# BQH_DATN_PI4.net
KiCad netlist of a schematic drawn in Altium Designer
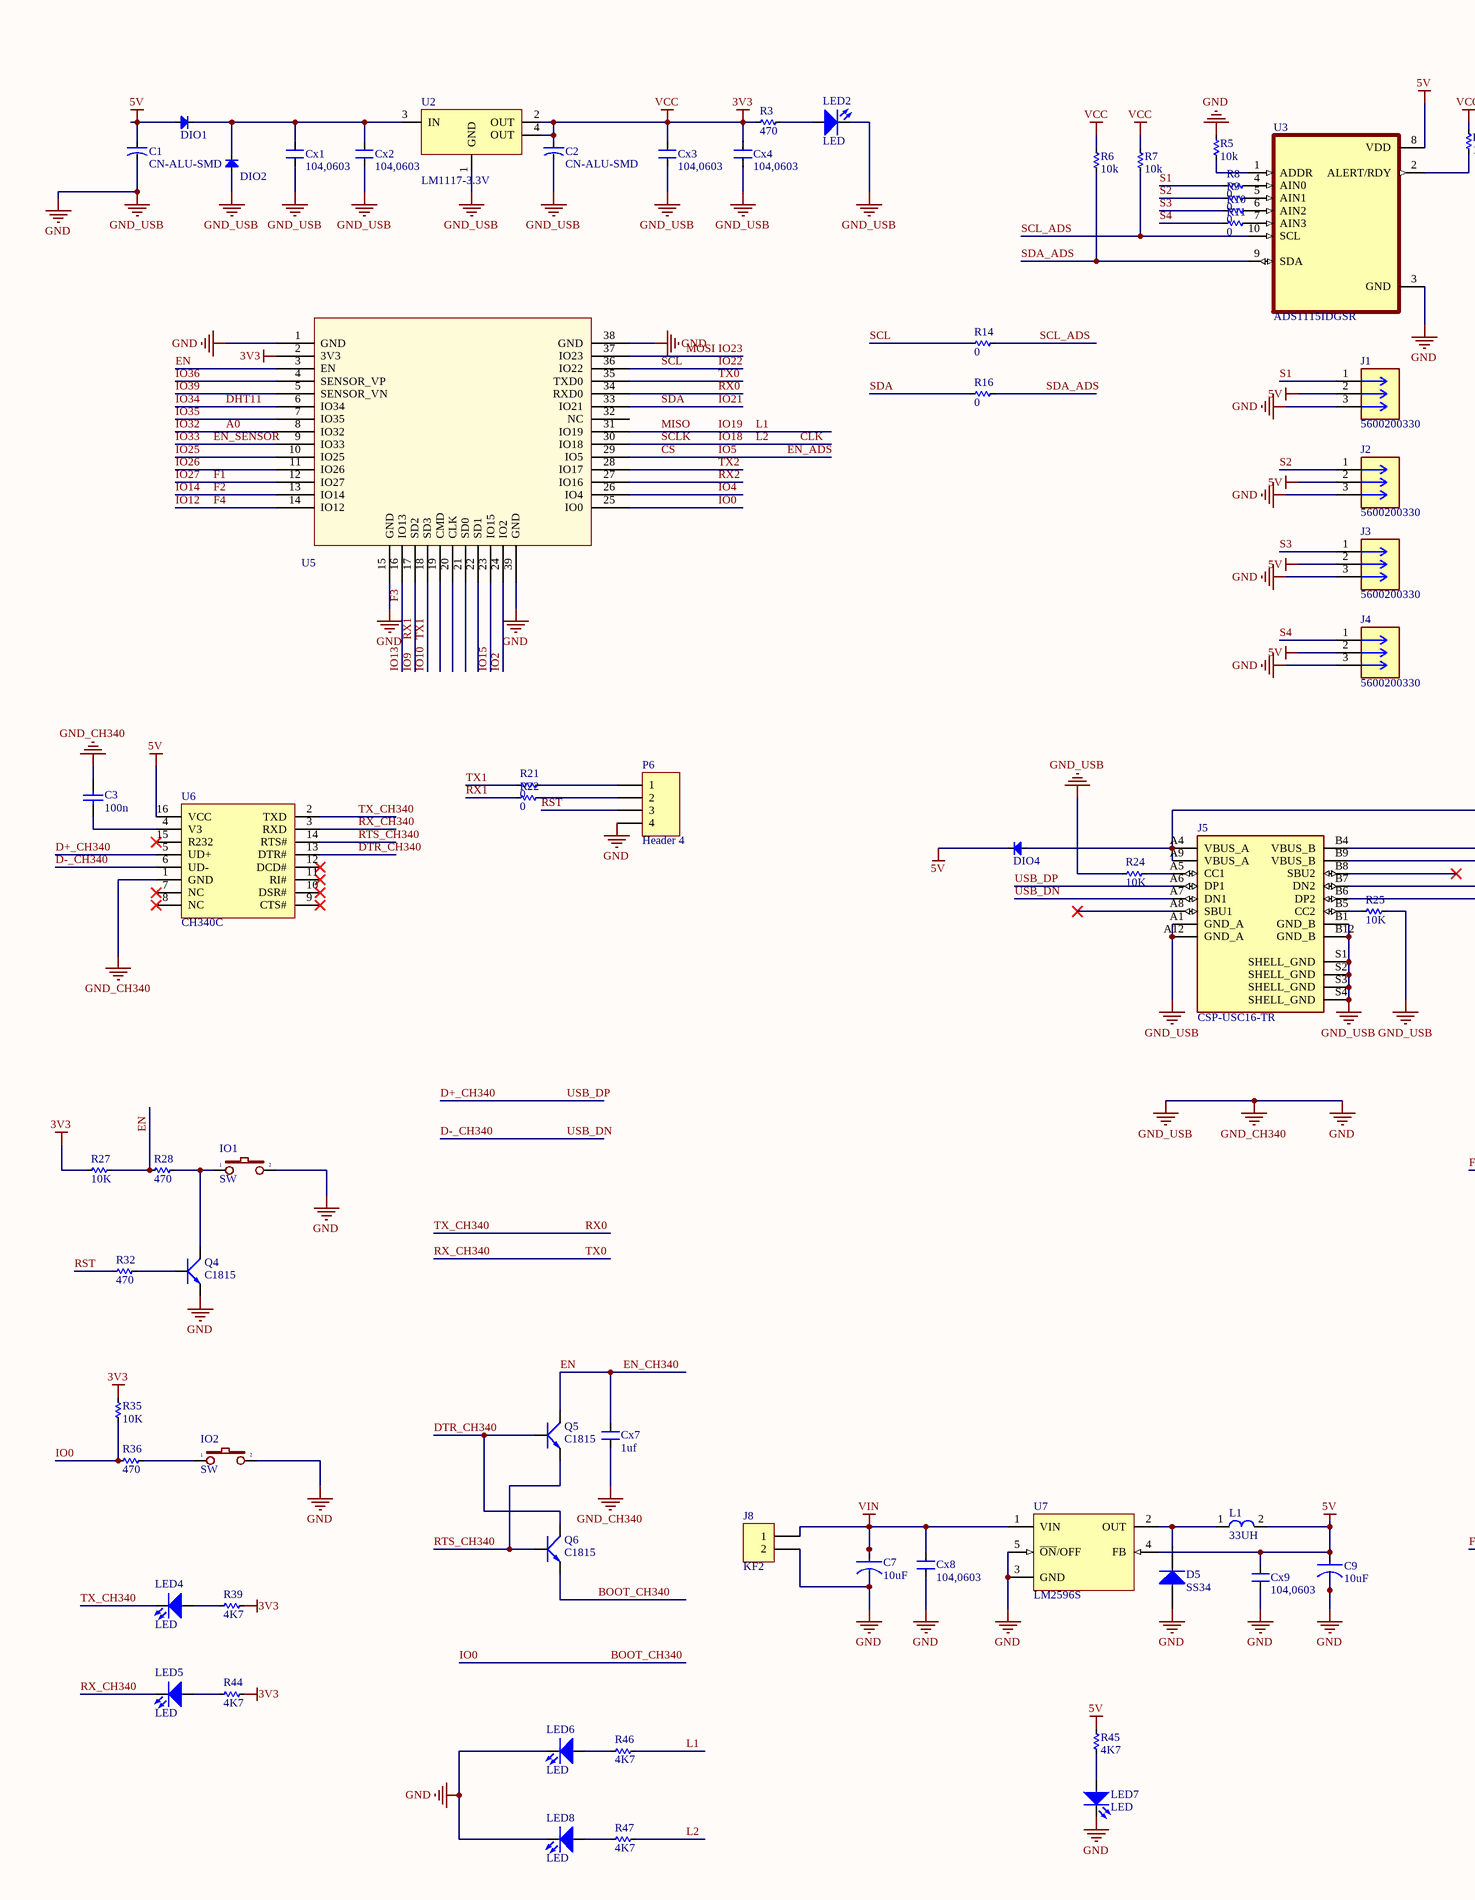
[diagram p0: BQH_DATN_PI4.SchDoc, left]
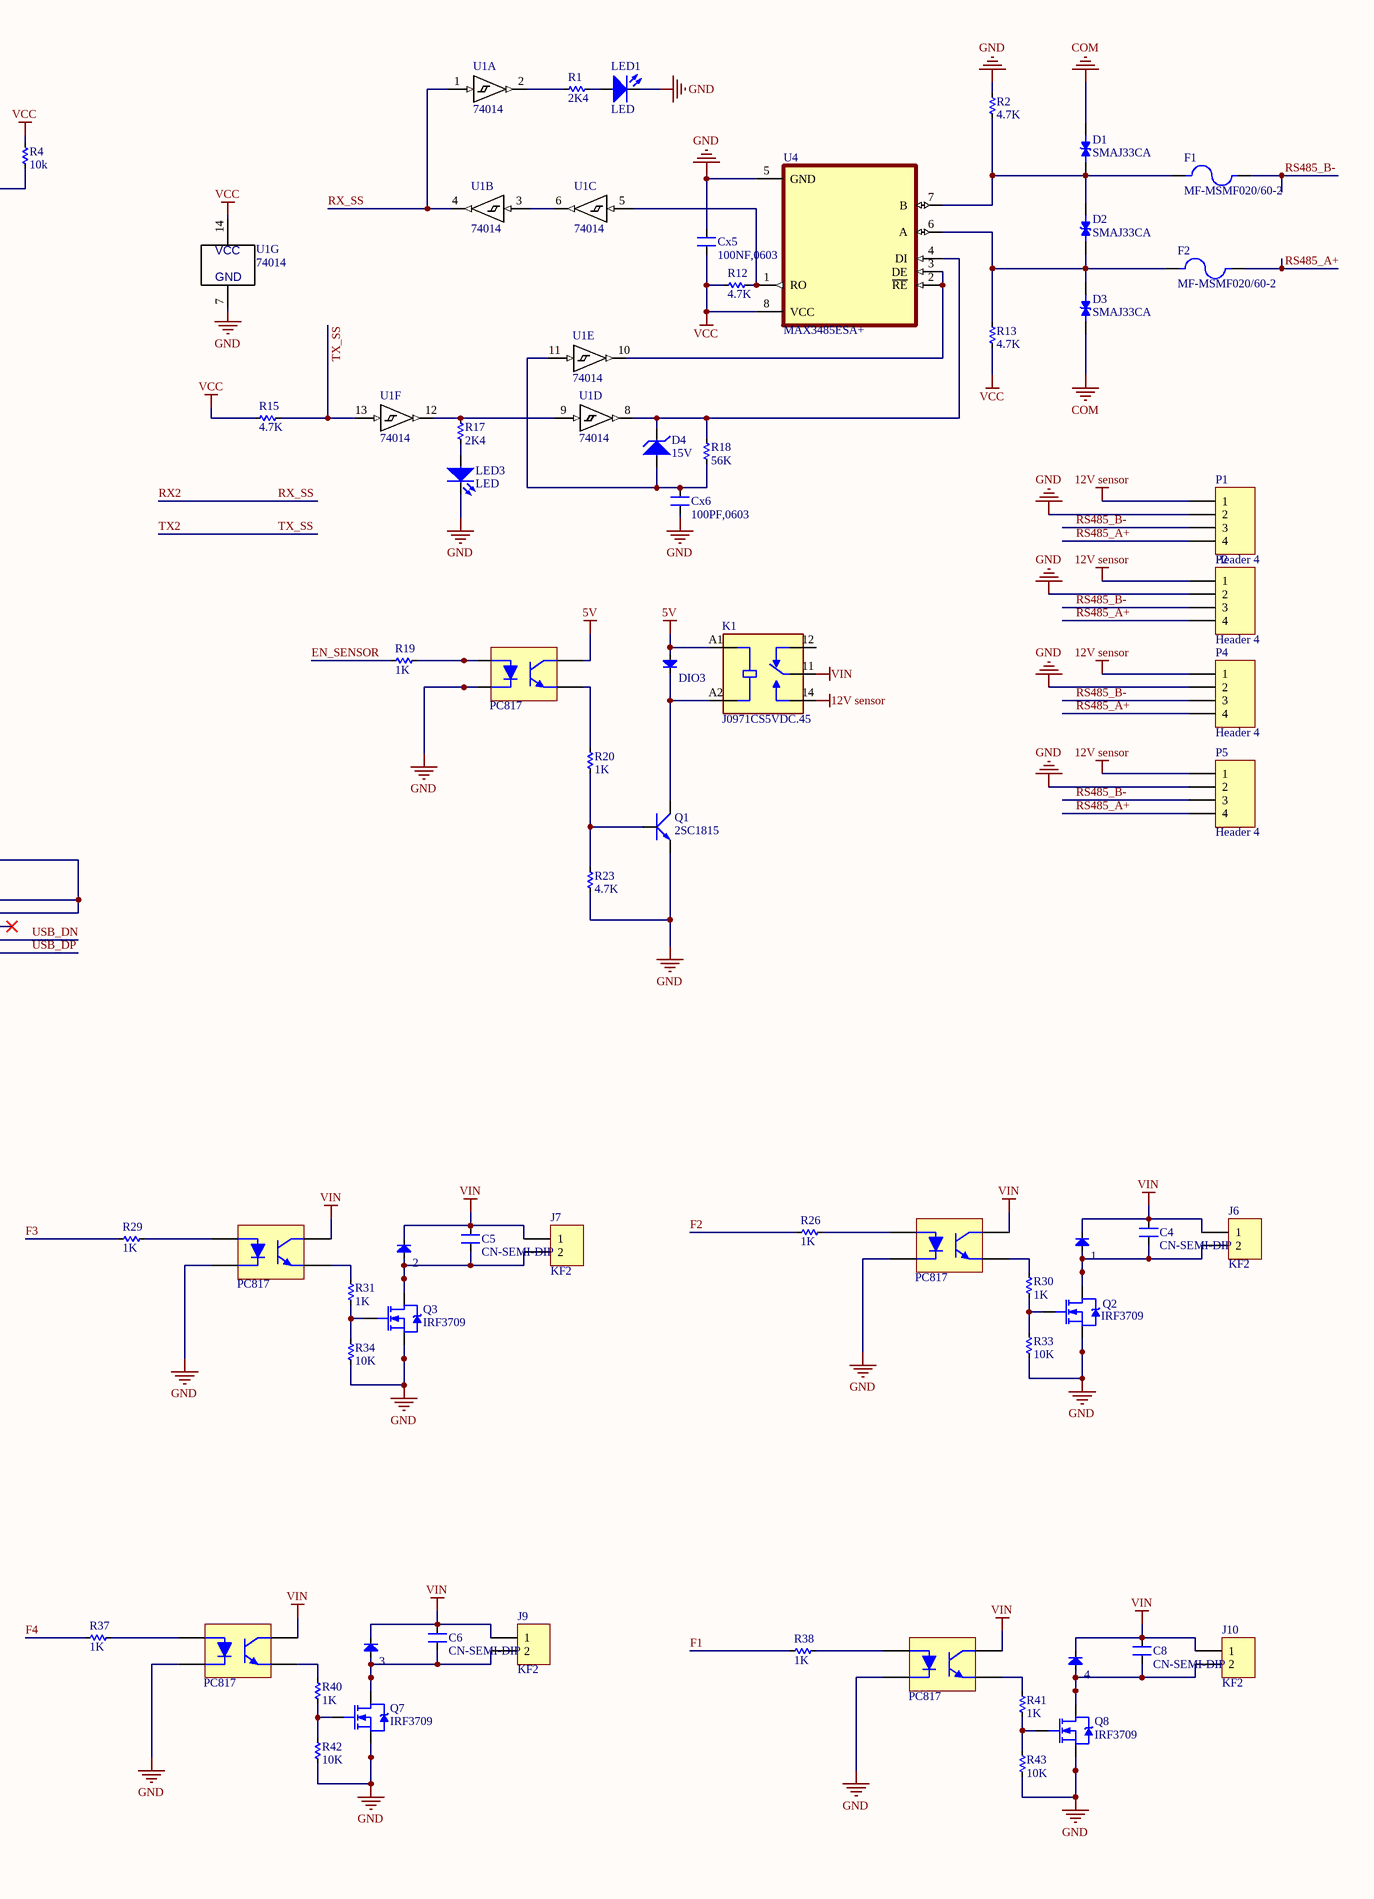
[diagram p1: BQH_DATN_PI4.SchDoc, right]

(export (version "E")
  (design (tool "Eeschema 10.0.6"))
  (components
    (comp (ref "1")
      (value "Diode SMD")
      (footprint "DIO-SMD-A")
      (description "Default Diode")
      (fields (field (name "PUBLISHER") "Altium Limited"))
      (libsource (lib "Lib by Quang") (part "Diode SMD"))
    )
    (comp (ref "2")
      (value "Diode SMD")
      (footprint "DIO-SMD-A")
      (description "Default Diode")
      (fields (field (name "PUBLISHER") "Altium Limited"))
      (libsource (lib "Lib by Quang") (part "Diode SMD"))
    )
    (comp (ref "3")
      (value "Diode SMD")
      (footprint "DIO-SMD-A")
      (description "Default Diode")
      (fields (field (name "PUBLISHER") "Altium Limited"))
      (libsource (lib "Lib by Quang") (part "Diode SMD"))
    )
    (comp (ref "4")
      (value "Diode SMD")
      (footprint "DIO-SMD-A")
      (description "Default Diode")
      (fields (field (name "PUBLISHER") "Altium Limited"))
      (libsource (lib "Lib by Quang") (part "Diode SMD"))
    )
    (comp (ref "C1")
      (value "CN-ALU-SMD")
      (footprint "CAP-ALU-SMD-6.3x7.7x2.2")
      (description "Polarized Capacitor (Axial)")
      (fields (field (name "PUBLISHER") "Altium Limited"))
      (libsource (lib "Lib by Quang") (part "CN-ALU-SMD"))
    )
    (comp (ref "C2")
      (value "CN-ALU-SMD")
      (footprint "CAP-ALU-SMD-6.3x7.7x2.2")
      (description "Polarized Capacitor (Axial)")
      (fields (field (name "PUBLISHER") "Altium Limited"))
      (libsource (lib "Lib by Quang") (part "CN-ALU-SMD"))
    )
    (comp (ref "C3")
      (value "100n")
      (footprint "CAP SMD 0805.CAOVANHUONG")
      (description "Ceramic capacitor")
      (libsource (lib "Lib by Quang") (part "Capacitor NP"))
    )
    (comp (ref "C4")
      (value "CN-SEMI-DIP")
      (footprint "C-SE-10x13x12x6x4")
      (description "Capacitor (Semiconductor SIM Model)")
      (fields (field (name "PUBLISHER") "Altium Limited"))
      (libsource (lib "Lib by Quang") (part "CN-SEMI-DIP"))
    )
    (comp (ref "C5")
      (value "CN-SEMI-DIP")
      (footprint "C-SE-10x13x12x6x4")
      (description "Capacitor (Semiconductor SIM Model)")
      (fields (field (name "PUBLISHER") "Altium Limited"))
      (libsource (lib "Lib by Quang") (part "CN-SEMI-DIP"))
    )
    (comp (ref "C6")
      (value "CN-SEMI-DIP")
      (footprint "C-SE-10x13x12x6x4")
      (description "Capacitor (Semiconductor SIM Model)")
      (fields (field (name "PUBLISHER") "Altium Limited"))
      (libsource (lib "Lib by Quang") (part "CN-SEMI-DIP"))
    )
    (comp (ref "C7")
      (value "10uF")
      (footprint "CAP 8x11.5x3.5mm.CAOVANHUONG")
      (description "Alumium capacitor")
      (libsource (lib "Lib by Quang") (part "Capacitor"))
    )
    (comp (ref "C8")
      (value "CN-SEMI-DIP")
      (footprint "C-SE-10x13x12x6x4")
      (description "Capacitor (Semiconductor SIM Model)")
      (fields (field (name "PUBLISHER") "Altium Limited"))
      (libsource (lib "Lib by Quang") (part "CN-SEMI-DIP"))
    )
    (comp (ref "C9")
      (value "10uF")
      (footprint "CAP 8x11.5x3.5mm.CAOVANHUONG")
      (description "Alumium capacitor")
      (libsource (lib "Lib by Quang") (part "Capacitor"))
    )
    (comp (ref "Cx1")
      (value "104,0603")
      (footprint "CN-SMD-3225")
      (libsource (lib "Lib by Quang") (part "CN"))
    )
    (comp (ref "Cx2")
      (value "104,0603")
      (footprint "CN-SMD-0805")
      (libsource (lib "Lib by Quang") (part "CN"))
    )
    (comp (ref "Cx3")
      (value "104,0603")
      (footprint "CN-SMD-3225")
      (libsource (lib "Lib by Quang") (part "CN"))
    )
    (comp (ref "Cx4")
      (value "104,0603")
      (footprint "CN-SMD-0805")
      (libsource (lib "Lib by Quang") (part "CN"))
    )
    (comp (ref "Cx5")
      (value "100NF,0603")
      (footprint "CN-SMD-0805")
      (libsource (lib "Lib by Quang") (part "CN"))
    )
    (comp (ref "Cx6")
      (value "100PF,0603")
      (footprint "CN-SMD-0805")
      (libsource (lib "Lib by Quang") (part "CN"))
    )
    (comp (ref "Cx7") (value "1uf") (footprint "CN-SMD-0805") (libsource (lib "Lib by Quang") (part "CN")))
    (comp (ref "Cx8")
      (value "104,0603")
      (footprint "CN-SMD-3225")
      (libsource (lib "Lib by Quang") (part "CN"))
    )
    (comp (ref "Cx9")
      (value "104,0603")
      (footprint "CN-SMD-3225")
      (libsource (lib "Lib by Quang") (part "CN"))
    )
    (comp (ref "D1")
      (value "SMAJ33CA")
      (footprint "DIOM4325X250N")
      (description "69.7V Clamp 33A (8/20Âµs) Ipp Tvs Diode Surface Mount SMA (DO-214AC)")
      (fields (field (name "MF") "STMicroelectronics") (field (name "MP") "SMAJ33CA-TR"))
      (libsource (lib "SMAJ33CA (1)") (part "SMAJ33CA"))
    )
    (comp (ref "D2")
      (value "SMAJ33CA")
      (footprint "DIOM4325X250N")
      (description "69.7V Clamp 33A (8/20Âµs) Ipp Tvs Diode Surface Mount SMA (DO-214AC)")
      (fields (field (name "MF") "STMicroelectronics") (field (name "MP") "SMAJ33CA-TR"))
      (libsource (lib "SMAJ33CA (1)") (part "SMAJ33CA"))
    )
    (comp (ref "D3")
      (value "SMAJ33CA")
      (footprint "DIOM4325X250N")
      (description "69.7V Clamp 33A (8/20Âµs) Ipp Tvs Diode Surface Mount SMA (DO-214AC)")
      (fields (field (name "MF") "STMicroelectronics") (field (name "MP") "SMAJ33CA-TR"))
      (libsource (lib "SMAJ33CA (1)") (part "SMAJ33CA"))
    )
    (comp (ref "D4")
      (value "15V")
      (footprint "SOD80.CAOVANHUONG")
      (description "Diode Zener")
      (fields (field (name "PART NUMBER") "BZV55-C5V1"))
      (libsource (lib "Lib by Quang") (part "Diode Zener"))
    )
    (comp (ref "D5")
      (value "SS34")
      (footprint "DIODE SMA")
      (description "Dán")
      (libsource (lib "Diode") (part "Diode SS34 ( 1N5822 )"))
    )
    (comp (ref "DIO1")
      (value "Diode SMD")
      (footprint "DIO-SMD-106")
      (description "Default Diode")
      (fields (field (name "PUBLISHER") "Altium Limited"))
      (libsource (lib "Lib by Quang") (part "Diode SMD"))
    )
    (comp (ref "DIO2")
      (value "Diode SMD")
      (footprint "DIO-SMD-106")
      (description "Default Diode")
      (fields (field (name "PUBLISHER") "Altium Limited"))
      (libsource (lib "Lib by Quang") (part "Diode SMD"))
    )
    (comp (ref "DIO3")
      (value "Diode SMD")
      (footprint "DIO-SMD-106")
      (description "Default Diode")
      (fields (field (name "PUBLISHER") "Altium Limited"))
      (libsource (lib "Lib by Quang") (part "Diode SMD"))
    )
    (comp (ref "DIO4")
      (value "Diode SMD")
      (footprint "DIO-SMD-106")
      (description "Default Diode")
      (fields (field (name "PUBLISHER") "Altium Limited"))
      (libsource (lib "Lib by Quang") (part "Diode SMD"))
    )
    (comp (ref "F1")
      (value "MF-MSMF020/60-2")
      (footprint "FUSER_MF-MSMF020/60-2")
      (description "Polymeric PTC Resettable Fuse 60V 200mA Ih Surface Mount 1812 (4532 Metric), Concave")
      (fields (field (name "MF") "Bourns"))
      (libsource (lib "MF-MSMF020_60-2 (1)") (part "MF-MSMF020/60-2"))
    )
    (comp (ref "F2")
      (value "MF-MSMF020/60-2")
      (footprint "FUSER_MF-MSMF020/60-2")
      (description "Polymeric PTC Resettable Fuse 60V 200mA Ih Surface Mount 1812 (4532 Metric), Concave")
      (fields (field (name "MF") "Bourns"))
      (libsource (lib "MF-MSMF020_60-2 (1)") (part "MF-MSMF020/60-2"))
    )
    (comp (ref "IO1")
      (value "SW")
      (footprint "SW1-SMD")
      (description "Switch button 2 pin")
      (libsource (lib "LIBRARY") (part "SW2"))
    )
    (comp (ref "IO2")
      (value "SW")
      (footprint "SW1-SMD")
      (description "Switch button 2 pin")
      (libsource (lib "LIBRARY") (part "SW2"))
    )
    (comp (ref "J1")
      (value "5600200330")
      (footprint "CONN03_560020_MOL")
      (libsource (lib "5600200330") (part "5600200330"))
    )
    (comp (ref "J2")
      (value "5600200330")
      (footprint "CONN03_560020_MOL")
      (libsource (lib "5600200330") (part "5600200330"))
    )
    (comp (ref "J3")
      (value "5600200330")
      (footprint "CONN03_560020_MOL")
      (libsource (lib "5600200330") (part "5600200330"))
    )
    (comp (ref "J4")
      (value "5600200330")
      (footprint "CONN03_560020_MOL")
      (libsource (lib "5600200330") (part "5600200330"))
    )
    (comp (ref "J5")
      (value "CSP-USC16-TR")
      (footprint "VALCON_CSP-USC16-TR")
      (description "CSP-USC16-TR Valcon USB Type C Surface Mount PCB Socket")
      (fields (field (name "MF") "Valcon"))
      (libsource (lib "CSP-USC16-TR") (part "CSP-USC16-TR"))
    )
    (comp (ref "J6")
      (value "KF2")
      (footprint "KF2-7.62")
      (fields
        (field (name "MANUFACTURER") "Würth Elektronik eiSos GmbH")
        (field (name "PARTNO") "691103110002")
        (field (name "CREATED BY") "Karrer Zheng")
      )
      (libsource (lib "") (part "KF2_1"))
    )
    (comp (ref "J7")
      (value "KF2")
      (footprint "KF2-7.62")
      (fields
        (field (name "MANUFACTURER") "Würth Elektronik eiSos GmbH")
        (field (name "PARTNO") "691103110002")
        (field (name "CREATED BY") "Karrer Zheng")
      )
      (libsource (lib "") (part "KF2_1"))
    )
    (comp (ref "J8")
      (value "KF2")
      (footprint "KF2-7.62")
      (fields
        (field (name "MANUFACTURER") "Würth Elektronik eiSos GmbH")
        (field (name "PARTNO") "691103110002")
        (field (name "CREATED BY") "Karrer Zheng")
      )
      (libsource (lib "LIBRARY") (part "KF2"))
    )
    (comp (ref "J9")
      (value "KF2")
      (footprint "KF2-7.62")
      (fields
        (field (name "MANUFACTURER") "Würth Elektronik eiSos GmbH")
        (field (name "PARTNO") "691103110002")
        (field (name "CREATED BY") "Karrer Zheng")
      )
      (libsource (lib "") (part "KF2_1"))
    )
    (comp (ref "J10")
      (value "KF2")
      (footprint "KF2-7.62")
      (fields
        (field (name "MANUFACTURER") "Würth Elektronik eiSos GmbH")
        (field (name "PARTNO") "691103110002")
        (field (name "CREATED BY") "Karrer Zheng")
      )
      (libsource (lib "") (part "KF2_1"))
    )
    (comp (ref "K1")
      (value "J0971CS5VDC.45")
      (footprint "RELAY_J0971CS5VDC.45")
      (description "General Purpose Relay SPDT (1 Form C) 5VDC Coil Through Hole")
      (fields (field (name "MF") "CIT Relay and Switch"))
      (libsource (lib "J0971CS5VDC.45") (part "J0971CS5VDC.45"))
    )
    (comp (ref "L1")
      (value "33UH")
      (footprint "L-SMD-M-7.3x4.5")
      (fields
        (field (name "PARTNO") "78477010")
        (field (name "MANUFACTURER") "Wurth Elektronik")
        (field (name "CREATED BY") "Baojun Chen")
      )
      (libsource (lib "LIBRARY") (part "L-SMD-1"))
    )
    (comp (ref "LED1")
      (value "LED")
      (footprint "LED SMD 0603 RED.CAOVANHUONG")
      (description "LED Single")
      (libsource (lib "Lib by Quang") (part "LED"))
    )
    (comp (ref "LED2")
      (value "LED")
      (footprint "LED SMD 0805 RED witch hole.CAOVANHUONG")
      (description "LED Single")
      (libsource (lib "Lib by Quang") (part "LED"))
    )
    (comp (ref "LED3")
      (value "LED")
      (footprint "LED SMD 0603 RED.CAOVANHUONG")
      (description "LED Single")
      (libsource (lib "Lib by Quang") (part "LED"))
    )
    (comp (ref "LED4")
      (value "LED")
      (footprint "LED SMD 0603 RED.CAOVANHUONG")
      (description "LED Single")
      (libsource (lib "Lib by Quang") (part "LED"))
    )
    (comp (ref "LED5")
      (value "LED")
      (footprint "LED SMD 0603 RED.CAOVANHUONG")
      (description "LED Single")
      (libsource (lib "Lib by Quang") (part "LED"))
    )
    (comp (ref "LED6")
      (value "LED")
      (footprint "LED SMD 0603 RED.CAOVANHUONG")
      (description "LED Single")
      (libsource (lib "Lib by Quang") (part "LED"))
    )
    (comp (ref "LED7")
      (value "LED")
      (footprint "LED SMD 0805 YEL.CAOVANHUONG")
      (description "LED Single")
      (libsource (lib "Lib by Quang") (part "LED"))
    )
    (comp (ref "LED8")
      (value "LED")
      (footprint "LED SMD 0603 RED.CAOVANHUONG")
      (description "LED Single")
      (libsource (lib "Lib by Quang") (part "LED"))
    )
    (comp (ref "P1")
      (value "Header 4")
      (footprint "PCB HEADER 4PIN.CAOVANHUONG")
      (description "Header, 4-Pin")
      (fields (field (name "PUBLISHER") "Altium Limited"))
      (libsource (lib "Lib by Quang") (part "Header 4"))
    )
    (comp (ref "P2")
      (value "Header 4")
      (footprint "PCB HEADER 4PIN.CAOVANHUONG")
      (description "Header, 4-Pin")
      (fields (field (name "PUBLISHER") "Altium Limited"))
      (libsource (lib "Lib by Quang") (part "Header 4"))
    )
    (comp (ref "P3")
      (value "PC817")
      (footprint "PC817S.CAOVANHUONG")
      (description "NPN PHOTO General Purpose Amplifier")
      (fields (field (name "PUBLISHER") "Altium Limited"))
      (libsource (lib "Lib by Quang") (part "PC817"))
    )
    (comp (ref "P4")
      (value "Header 4")
      (footprint "PCB HEADER 4PIN.CAOVANHUONG")
      (description "Header, 4-Pin")
      (fields (field (name "PUBLISHER") "Altium Limited"))
      (libsource (lib "Lib by Quang") (part "Header 4"))
    )
    (comp (ref "P5")
      (value "Header 4")
      (footprint "PCB HEADER 4PIN.CAOVANHUONG")
      (description "Header, 4-Pin")
      (fields (field (name "PUBLISHER") "Altium Limited"))
      (libsource (lib "Lib by Quang") (part "Header 4"))
    )
    (comp (ref "P6")
      (value "Header 4")
      (footprint "PCB HEADER 4PIN.CAOVANHUONG")
      (description "Header, 4-Pin")
      (fields (field (name "PUBLISHER") "Altium Limited"))
      (libsource (lib "Lib by Quang") (part "Header 4"))
    )
    (comp (ref "P7")
      (value "PC817")
      (footprint "PC817S.CAOVANHUONG")
      (description "NPN PHOTO General Purpose Amplifier")
      (fields (field (name "PUBLISHER") "Altium Limited"))
      (libsource (lib "Lib by Quang") (part "PC817"))
    )
    (comp (ref "P8")
      (value "PC817")
      (footprint "PC817S.CAOVANHUONG")
      (description "NPN PHOTO General Purpose Amplifier")
      (fields (field (name "PUBLISHER") "Altium Limited"))
      (libsource (lib "Lib by Quang") (part "PC817"))
    )
    (comp (ref "P9")
      (value "PC817")
      (footprint "PC817S.CAOVANHUONG")
      (description "NPN PHOTO General Purpose Amplifier")
      (fields (field (name "PUBLISHER") "Altium Limited"))
      (libsource (lib "Lib by Quang") (part "PC817"))
    )
    (comp (ref "P10")
      (value "PC817")
      (footprint "PC817S.CAOVANHUONG")
      (description "NPN PHOTO General Purpose Amplifier")
      (fields (field (name "PUBLISHER") "Altium Limited"))
      (libsource (lib "Lib by Quang") (part "PC817"))
    )
    (comp (ref "Q1")
      (value "2SC1815")
      (footprint "SOT23-321")
      (description "NPN 600mW, ECB")
      (libsource (lib "LIBRARY") (part "2SC1815"))
    )
    (comp (ref "Q2")
      (value "IRF3709")
      (footprint "D2PAK")
      (description "N-Channel Power MOSFET")
      (libsource (lib "TranFet") (part "IRF3709S SMD"))
    )
    (comp (ref "Q3")
      (value "IRF3709")
      (footprint "D2PAK")
      (description "N-Channel Power MOSFET")
      (libsource (lib "TranFet") (part "IRF3709S SMD"))
    )
    (comp (ref "Q4")
      (value "C1815")
      (footprint "SOT23-3.CAOVANHUONG")
      (description "NPN Transistor, Ic=150mA")
      (libsource (lib "Lib by Quang") (part "C1815"))
    )
    (comp (ref "Q5")
      (value "C1815")
      (footprint "SOT23-3.CAOVANHUONG")
      (description "NPN Transistor, Ic=150mA")
      (libsource (lib "Lib by Quang") (part "C1815"))
    )
    (comp (ref "Q6")
      (value "C1815")
      (footprint "SOT23-3.CAOVANHUONG")
      (description "NPN Transistor, Ic=150mA")
      (libsource (lib "Lib by Quang") (part "C1815"))
    )
    (comp (ref "Q7")
      (value "IRF3709")
      (footprint "D2PAK")
      (description "N-Channel Power MOSFET")
      (libsource (lib "TranFet") (part "IRF3709S SMD"))
    )
    (comp (ref "Q8")
      (value "IRF3709")
      (footprint "D2PAK")
      (description "N-Channel Power MOSFET")
      (libsource (lib "TranFet") (part "IRF3709S SMD"))
    )
    (comp (ref "R1")
      (value "2K4")
      (footprint "RES-SMD-0805")
      (description "Resistor")
      (fields
        (field (name "MANUFACTURER") "Generic Components")
        (field (name "PUBLISHER") "Altium Hobart Technology Centre")
      )
      (libsource (lib "LIBRARY") (part "Res-SMD"))
    )
    (comp (ref "R2")
      (value "4.7K")
      (footprint "RES-SMD-0805")
      (description "Resistor")
      (fields
        (field (name "MANUFACTURER") "Generic Components")
        (field (name "PUBLISHER") "Altium Hobart Technology Centre")
      )
      (libsource (lib "LIBRARY") (part "Res-SMD"))
    )
    (comp (ref "R3")
      (value "470")
      (footprint "RES-SMD-0805")
      (description "Resistor")
      (fields
        (field (name "MANUFACTURER") "Generic Components")
        (field (name "PUBLISHER") "Altium Hobart Technology Centre")
      )
      (libsource (lib "LIBRARY") (part "Res-SMD"))
    )
    (comp (ref "R4")
      (value "10k")
      (footprint "RES-SMD-0805")
      (description "Resistor")
      (fields
        (field (name "MANUFACTURER") "Generic Components")
        (field (name "PUBLISHER") "Altium Hobart Technology Centre")
      )
      (libsource (lib "LIBRARY") (part "Res-SMD"))
    )
    (comp (ref "R5")
      (value "10k")
      (footprint "RES-SMD-0805")
      (description "Resistor")
      (fields
        (field (name "MANUFACTURER") "Generic Components")
        (field (name "PUBLISHER") "Altium Hobart Technology Centre")
      )
      (libsource (lib "LIBRARY") (part "Res-SMD"))
    )
    (comp (ref "R6")
      (value "10k")
      (footprint "RES-SMD-0805")
      (description "Resistor")
      (fields
        (field (name "MANUFACTURER") "Generic Components")
        (field (name "PUBLISHER") "Altium Hobart Technology Centre")
      )
      (libsource (lib "LIBRARY") (part "Res-SMD"))
    )
    (comp (ref "R7")
      (value "10k")
      (footprint "RES-SMD-0805")
      (description "Resistor")
      (fields
        (field (name "MANUFACTURER") "Generic Components")
        (field (name "PUBLISHER") "Altium Hobart Technology Centre")
      )
      (libsource (lib "LIBRARY") (part "Res-SMD"))
    )
    (comp (ref "R8")
      (value "0")
      (footprint "RES-SMD-0805")
      (description "Resistor")
      (fields
        (field (name "MANUFACTURER") "Generic Components")
        (field (name "PUBLISHER") "Altium Hobart Technology Centre")
      )
      (libsource (lib "LIBRARY") (part "Res-SMD"))
    )
    (comp (ref "R9")
      (value "0")
      (footprint "RES-SMD-0805")
      (description "Resistor")
      (fields
        (field (name "MANUFACTURER") "Generic Components")
        (field (name "PUBLISHER") "Altium Hobart Technology Centre")
      )
      (libsource (lib "LIBRARY") (part "Res-SMD"))
    )
    (comp (ref "R10")
      (value "0")
      (footprint "RES-SMD-0805")
      (description "Resistor")
      (fields
        (field (name "MANUFACTURER") "Generic Components")
        (field (name "PUBLISHER") "Altium Hobart Technology Centre")
      )
      (libsource (lib "LIBRARY") (part "Res-SMD"))
    )
    (comp (ref "R11")
      (value "0")
      (footprint "RES-SMD-0805")
      (description "Resistor")
      (fields
        (field (name "MANUFACTURER") "Generic Components")
        (field (name "PUBLISHER") "Altium Hobart Technology Centre")
      )
      (libsource (lib "LIBRARY") (part "Res-SMD"))
    )
    (comp (ref "R12")
      (value "4.7K")
      (footprint "RES-SMD-0805")
      (description "Resistor")
      (fields
        (field (name "MANUFACTURER") "Generic Components")
        (field (name "PUBLISHER") "Altium Hobart Technology Centre")
      )
      (libsource (lib "LIBRARY") (part "Res-SMD"))
    )
    (comp (ref "R13")
      (value "4.7K")
      (footprint "RES-SMD-0805")
      (description "Resistor")
      (fields
        (field (name "MANUFACTURER") "Generic Components")
        (field (name "PUBLISHER") "Altium Hobart Technology Centre")
      )
      (libsource (lib "LIBRARY") (part "Res-SMD"))
    )
    (comp (ref "R14")
      (value "0")
      (footprint "RES-SMD-0805")
      (description "Resistor")
      (fields
        (field (name "MANUFACTURER") "Generic Components")
        (field (name "PUBLISHER") "Altium Hobart Technology Centre")
      )
      (libsource (lib "LIBRARY") (part "Res-SMD"))
    )
    (comp (ref "R15")
      (value "4.7K")
      (footprint "RES-SMD-0805")
      (description "Resistor")
      (fields
        (field (name "MANUFACTURER") "Generic Components")
        (field (name "PUBLISHER") "Altium Hobart Technology Centre")
      )
      (libsource (lib "LIBRARY") (part "Res-SMD"))
    )
    (comp (ref "R16")
      (value "0")
      (footprint "RES-SMD-0805")
      (description "Resistor")
      (fields
        (field (name "MANUFACTURER") "Generic Components")
        (field (name "PUBLISHER") "Altium Hobart Technology Centre")
      )
      (libsource (lib "LIBRARY") (part "Res-SMD"))
    )
    (comp (ref "R17")
      (value "2K4")
      (footprint "RES-SMD-0805")
      (description "Resistor")
      (fields
        (field (name "MANUFACTURER") "Generic Components")
        (field (name "PUBLISHER") "Altium Hobart Technology Centre")
      )
      (libsource (lib "LIBRARY") (part "Res-SMD"))
    )
    (comp (ref "R18")
      (value "56K")
      (footprint "RES-SMD-0805")
      (description "Resistor")
      (fields
        (field (name "MANUFACTURER") "Generic Components")
        (field (name "PUBLISHER") "Altium Hobart Technology Centre")
      )
      (libsource (lib "LIBRARY") (part "Res-SMD"))
    )
    (comp (ref "R19")
      (value "1K")
      (footprint "RES-SMD-0805")
      (description "Resistor")
      (fields
        (field (name "MANUFACTURER") "Generic Components")
        (field (name "PUBLISHER") "Altium Hobart Technology Centre")
      )
      (libsource (lib "LIBRARY") (part "Res-SMD"))
    )
    (comp (ref "R20")
      (value "1K")
      (footprint "RES-SMD-0805")
      (description "Resistor")
      (fields
        (field (name "MANUFACTURER") "Generic Components")
        (field (name "PUBLISHER") "Altium Hobart Technology Centre")
      )
      (libsource (lib "LIBRARY") (part "Res-SMD"))
    )
    (comp (ref "R21")
      (value "0")
      (footprint "RES-SMD-0805")
      (description "Resistor")
      (fields
        (field (name "MANUFACTURER") "Generic Components")
        (field (name "PUBLISHER") "Altium Hobart Technology Centre")
      )
      (libsource (lib "LIBRARY") (part "Res-SMD"))
    )
    (comp (ref "R22")
      (value "0")
      (footprint "RES-SMD-0805")
      (description "Resistor")
      (fields
        (field (name "MANUFACTURER") "Generic Components")
        (field (name "PUBLISHER") "Altium Hobart Technology Centre")
      )
      (libsource (lib "LIBRARY") (part "Res-SMD"))
    )
    (comp (ref "R23")
      (value "4.7K")
      (footprint "RES-SMD-0805")
      (description "Resistor")
      (fields
        (field (name "MANUFACTURER") "Generic Components")
        (field (name "PUBLISHER") "Altium Hobart Technology Centre")
      )
      (libsource (lib "LIBRARY") (part "Res-SMD"))
    )
    (comp (ref "R24")
      (value "10K")
      (footprint "RES-SMD-0805")
      (description "Resistor")
      (fields
        (field (name "MANUFACTURER") "Generic Components")
        (field (name "PUBLISHER") "Altium Hobart Technology Centre")
      )
      (libsource (lib "Lib by Quang") (part "Res-SMD"))
    )
    (comp (ref "R25")
      (value "10K")
      (footprint "RES-SMD-0805")
      (description "Resistor")
      (fields
        (field (name "MANUFACTURER") "Generic Components")
        (field (name "PUBLISHER") "Altium Hobart Technology Centre")
      )
      (libsource (lib "Lib by Quang") (part "Res-SMD"))
    )
    (comp (ref "R26")
      (value "1K")
      (footprint "RES-SMD-0805")
      (description "Resistor")
      (fields
        (field (name "MANUFACTURER") "Generic Components")
        (field (name "PUBLISHER") "Altium Hobart Technology Centre")
      )
      (libsource (lib "Lib by Quang") (part "Res-SMD"))
    )
    (comp (ref "R27")
      (value "10K")
      (footprint "RES-SMD-0805")
      (description "Resistor")
      (fields
        (field (name "MANUFACTURER") "Generic Components")
        (field (name "PUBLISHER") "Altium Hobart Technology Centre")
      )
      (libsource (lib "Lib by Quang") (part "Res-SMD"))
    )
    (comp (ref "R28")
      (value "470")
      (footprint "RES-SMD-0805")
      (description "Resistor")
      (fields
        (field (name "MANUFACTURER") "Generic Components")
        (field (name "PUBLISHER") "Altium Hobart Technology Centre")
      )
      (libsource (lib "Lib by Quang") (part "Res-SMD"))
    )
    (comp (ref "R29")
      (value "1K")
      (footprint "RES-SMD-0805")
      (description "Resistor")
      (fields
        (field (name "MANUFACTURER") "Generic Components")
        (field (name "PUBLISHER") "Altium Hobart Technology Centre")
      )
      (libsource (lib "Lib by Quang") (part "Res-SMD"))
    )
    (comp (ref "R30")
      (value "1K")
      (footprint "RES-SMD-0805")
      (description "Resistor")
      (fields
        (field (name "MANUFACTURER") "Generic Components")
        (field (name "PUBLISHER") "Altium Hobart Technology Centre")
      )
      (libsource (lib "Lib by Quang") (part "Res-SMD"))
    )
    (comp (ref "R31")
      (value "1K")
      (footprint "RES-SMD-0805")
      (description "Resistor")
      (fields
        (field (name "MANUFACTURER") "Generic Components")
        (field (name "PUBLISHER") "Altium Hobart Technology Centre")
      )
      (libsource (lib "Lib by Quang") (part "Res-SMD"))
    )
    (comp (ref "R32")
      (value "470")
      (footprint "RES-SMD-0603")
      (description "Resistor")
      (fields
        (field (name "MANUFACTURER") "Generic Components")
        (field (name "PUBLISHER") "Altium Hobart Technology Centre")
      )
      (libsource (lib "Lib by Quang") (part "Res-SMD"))
    )
    (comp (ref "R33")
      (value "10K")
      (footprint "RES-SMD-0805")
      (description "Resistor")
      (fields
        (field (name "MANUFACTURER") "Generic Components")
        (field (name "PUBLISHER") "Altium Hobart Technology Centre")
      )
      (libsource (lib "Lib by Quang") (part "Res-SMD"))
    )
    (comp (ref "R34")
      (value "10K")
      (footprint "RES-SMD-0805")
      (description "Resistor")
      (fields
        (field (name "MANUFACTURER") "Generic Components")
        (field (name "PUBLISHER") "Altium Hobart Technology Centre")
      )
      (libsource (lib "Lib by Quang") (part "Res-SMD"))
    )
    (comp (ref "R35")
      (value "10K")
      (footprint "RES-SMD-0805")
      (description "Resistor")
      (fields
        (field (name "MANUFACTURER") "Generic Components")
        (field (name "PUBLISHER") "Altium Hobart Technology Centre")
      )
      (libsource (lib "Lib by Quang") (part "Res-SMD"))
    )
    (comp (ref "R36")
      (value "470")
      (footprint "RES-SMD-0805")
      (description "Resistor")
      (fields
        (field (name "MANUFACTURER") "Generic Components")
        (field (name "PUBLISHER") "Altium Hobart Technology Centre")
      )
      (libsource (lib "Lib by Quang") (part "Res-SMD"))
    )
    (comp (ref "R37")
      (value "1K")
      (footprint "RES-SMD-0805")
      (description "Resistor")
      (fields
        (field (name "MANUFACTURER") "Generic Components")
        (field (name "PUBLISHER") "Altium Hobart Technology Centre")
      )
      (libsource (lib "Lib by Quang") (part "Res-SMD"))
    )
    (comp (ref "R38")
      (value "1K")
      (footprint "RES-SMD-0805")
      (description "Resistor")
      (fields
        (field (name "MANUFACTURER") "Generic Components")
        (field (name "PUBLISHER") "Altium Hobart Technology Centre")
      )
      (libsource (lib "Lib by Quang") (part "Res-SMD"))
    )
    (comp (ref "R39")
      (value "4K7")
      (footprint "RES-SMD-0805")
      (description "Resistor")
      (fields
        (field (name "MANUFACTURER") "Generic Components")
        (field (name "PUBLISHER") "Altium Hobart Technology Centre")
      )
      (libsource (lib "LIBRARY") (part "Res-SMD"))
    )
    (comp (ref "R40")
      (value "1K")
      (footprint "RES-SMD-0805")
      (description "Resistor")
      (fields
        (field (name "MANUFACTURER") "Generic Components")
        (field (name "PUBLISHER") "Altium Hobart Technology Centre")
      )
      (libsource (lib "Lib by Quang") (part "Res-SMD"))
    )
    (comp (ref "R41")
      (value "1K")
      (footprint "RES-SMD-0805")
      (description "Resistor")
      (fields
        (field (name "MANUFACTURER") "Generic Components")
        (field (name "PUBLISHER") "Altium Hobart Technology Centre")
      )
      (libsource (lib "Lib by Quang") (part "Res-SMD"))
    )
    (comp (ref "R42")
      (value "10K")
      (footprint "RES-SMD-0805")
      (description "Resistor")
      (fields
        (field (name "MANUFACTURER") "Generic Components")
        (field (name "PUBLISHER") "Altium Hobart Technology Centre")
      )
      (libsource (lib "Lib by Quang") (part "Res-SMD"))
    )
    (comp (ref "R43")
      (value "10K")
      (footprint "RES-SMD-0805")
      (description "Resistor")
      (fields
        (field (name "MANUFACTURER") "Generic Components")
        (field (name "PUBLISHER") "Altium Hobart Technology Centre")
      )
      (libsource (lib "Lib by Quang") (part "Res-SMD"))
    )
    (comp (ref "R44")
      (value "4K7")
      (footprint "RES-SMD-0805")
      (description "Resistor")
      (fields
        (field (name "MANUFACTURER") "Generic Components")
        (field (name "PUBLISHER") "Altium Hobart Technology Centre")
      )
      (libsource (lib "LIBRARY") (part "Res-SMD"))
    )
    (comp (ref "R45")
      (value "4K7")
      (footprint "RES-SMD-0805")
      (description "Resistor")
      (fields
        (field (name "MANUFACTURER") "Generic Components")
        (field (name "PUBLISHER") "Altium Hobart Technology Centre")
      )
      (libsource (lib "LIBRARY") (part "Res-SMD"))
    )
    (comp (ref "R46")
      (value "4K7")
      (footprint "RES-SMD-0805")
      (description "Resistor")
      (fields
        (field (name "MANUFACTURER") "Generic Components")
        (field (name "PUBLISHER") "Altium Hobart Technology Centre")
      )
      (libsource (lib "LIBRARY") (part "Res-SMD"))
    )
    (comp (ref "R47")
      (value "4K7")
      (footprint "RES-SMD-0805")
      (description "Resistor")
      (fields
        (field (name "MANUFACTURER") "Generic Components")
        (field (name "PUBLISHER") "Altium Hobart Technology Centre")
      )
      (libsource (lib "LIBRARY") (part "Res-SMD"))
    )
    (comp (ref "U1")
      (value "74014")
      (footprint "SO14")
      (description "IC, Hex Schmitttrigger Buffer, SO-14")
      (libsource (lib "Lib by Quang") (part "74HC7014"))
    )
    (comp (ref "U2")
      (value "LM1117-3.3V")
      (footprint "SOT223-4.CAOVANHUONG")
      (description "800mA Low-Dropout Linear Regulator")
      (fields (field (name "CREATOR") "Nguyen Ba Bien"))
      (libsource (lib "Lib by Quang") (part "LM1117"))
    )
    (comp (ref "U3")
      (value "ADS1115IDGSR")
      (footprint "SOP50P490X110-10N")
      (fields (field (name "MP") "altium_native_batch"))
      (libsource (lib "ADS1115IDGSR") (part "ADS1115IDGSR"))
    )
    (comp (ref "U4")
      (value "MAX3485ESA+")
      (footprint "SOIC127P600X175-8N")
      (description "1/1 Transceiver Half RS422, RS485 8-SOIC")
      (fields (field (name "MF") "Maxim Integrated"))
      (libsource (lib "MAX3485ESA_") (part "MAX3485ESA+"))
    )
    (comp (ref "U5")
      (value "ESP32-WROOM-32")
      (footprint "ESP32-WROOM-32D")
      (description "ESP32")
      (fields
        (field (name "MANUFACTURER") "Espressif Inc.")
        (field (name "PUBLISHER") "Cynetik Group")
        (field (name "REVIEWER") "Fenrrich")
        (field (name "DATA REVIEWER") "03-May-2019")
      )
      (libsource (lib "LIB_Lai") (part "ESP32-WROOM-32"))
    )
    (comp (ref "U6")
      (value "CH340C")
      (footprint "SOIC16_50_284_25X90_SMT")
      (description "USB Bridge, USB to UART USB 2.0 UART Interface")
      (fields (field (name "MANUFACTURER") "Olimex"))
      (libsource (lib "IC") (part "CH340C"))
    )
    (comp (ref "U7")
      (value "LM2596S")
      (footprint "TO263-5.CAOVANHUONG")
      (description "SIMPLE SWITCHER; 3A Step-Down Voltage Regulator")
      (fields
        (field (name "PARTNUMBER") "LM2596S-5.0")
        (field (name "MANUFACTURER") "National Semiconductor")
        (field (name "PUBLISHER") "Altium Limited")
      )
      (libsource (lib "Lib by Quang") (part "LM2596"))
    )
  )
  (nets
    (net (code "1") (name "/A0") (class "Default")
      (node (ref "U5") (pin "8") (pinfunction "IO32_8") (pintype "passive"))
    )
    (net (code "2") (name "/BOOT_CH340") (class "Default")
      (node (ref "Q6") (pin "2") (pinfunction "E_2") (pintype "passive"))
      (node (ref "R35") (pin "2") (pinfunction "2_2") (pintype "passive"))
      (node (ref "R36") (pin "2") (pinfunction "2_2") (pintype "passive"))
      (node (ref "U5") (pin "25") (pinfunction "IO0_25") (pintype "passive"))
    )
    (net (code "3") (name "/CLK") (class "Default")
      (node (ref "R47") (pin "2") (pinfunction "2_2") (pintype "passive"))
      (node (ref "U5") (pin "30") (pinfunction "IO18_30") (pintype "passive"))
    )
    (net (code "4") (name "/CS") (class "Default")
      (node (ref "U5") (pin "29") (pinfunction "IO5_29") (pintype "passive"))
    )
    (net (code "5") (name "/D+_CH340") (class "Default")
      (node (ref "J5") (pin "A6") (pinfunction "DP1_A6") (pintype "bidirectional"))
      (node (ref "J5") (pin "B6") (pinfunction "DP2_B6") (pintype "bidirectional"))
      (node (ref "U6") (pin "5") (pinfunction "UD+_5") (pintype "passive"))
    )
    (net (code "6") (name "/D-_CH340") (class "Default")
      (node (ref "J5") (pin "A7") (pinfunction "DN1_A7") (pintype "bidirectional"))
      (node (ref "J5") (pin "B7") (pinfunction "DN2_B7") (pintype "bidirectional"))
      (node (ref "U6") (pin "6") (pinfunction "UD-_6") (pintype "passive"))
    )
    (net (code "7") (name "/DHT11") (class "Default")
      (node (ref "U5") (pin "6") (pinfunction "IO34_6") (pintype "passive"))
    )
    (net (code "8") (name "/DTR_CH340") (class "Default")
      (node (ref "Q5") (pin "1") (pinfunction "B_1") (pintype "passive"))
      (node (ref "Q6") (pin "3") (pinfunction "C_3") (pintype "passive"))
      (node (ref "U6") (pin "13") (pinfunction "DTR#_13") (pintype "passive"))
    )
    (net (code "9") (name "/EN") (class "Default")
      (node (ref "Cx7") (pin "1") (pinfunction "1_1") (pintype "passive"))
      (node (ref "Q5") (pin "3") (pinfunction "C_3") (pintype "passive"))
      (node (ref "R27") (pin "2") (pinfunction "2_2") (pintype "passive"))
      (node (ref "R28") (pin "1") (pinfunction "1_1") (pintype "passive"))
      (node (ref "U5") (pin "3") (pinfunction "EN_3") (pintype "passive"))
    )
    (net (code "10") (name "/EN_SENSOR") (class "Default")
      (node (ref "R19") (pin "2") (pinfunction "2_2") (pintype "passive"))
      (node (ref "U5") (pin "9") (pinfunction "IO33_9") (pintype "passive"))
    )
    (net (code "11") (name "/F1") (class "Default")
      (node (ref "R38") (pin "1") (pinfunction "1_1") (pintype "passive"))
      (node (ref "U5") (pin "12") (pinfunction "IO27_12") (pintype "passive"))
    )
    (net (code "12") (name "/F2") (class "Default")
      (node (ref "R26") (pin "1") (pinfunction "1_1") (pintype "passive"))
      (node (ref "U5") (pin "13") (pinfunction "IO14_13") (pintype "passive"))
    )
    (net (code "13") (name "/F3") (class "Default")
      (node (ref "R29") (pin "1") (pinfunction "1_1") (pintype "passive"))
      (node (ref "U5") (pin "16") (pinfunction "IO13_16") (pintype "passive"))
    )
    (net (code "14") (name "/F4") (class "Default")
      (node (ref "R37") (pin "1") (pinfunction "1_1") (pintype "passive"))
      (node (ref "U5") (pin "14") (pinfunction "IO12_14") (pintype "passive"))
    )
    (net (code "15") (name "/IO2") (class "Default")
      (node (ref "U5") (pin "24") (pinfunction "IO2_24") (pintype "passive"))
    )
    (net (code "16") (name "/IO4") (class "Default")
      (node (ref "U5") (pin "26") (pinfunction "IO4_26") (pintype "passive"))
    )
    (net (code "17") (name "/IO9") (class "Default")
      (node (ref "R22") (pin "2") (pinfunction "2_2") (pintype "passive"))
      (node (ref "U5") (pin "17") (pinfunction "SD2_17") (pintype "passive"))
    )
    (net (code "18") (name "/IO10") (class "Default")
      (node (ref "R21") (pin "2") (pinfunction "2_2") (pintype "passive"))
      (node (ref "U5") (pin "18") (pinfunction "SD3_18") (pintype "passive"))
    )
    (net (code "19") (name "/IO15") (class "Default")
      (node (ref "U5") (pin "23") (pinfunction "IO15_23") (pintype "passive"))
    )
    (net (code "20") (name "/IO19") (class "Default")
      (node (ref "R46") (pin "2") (pinfunction "2_2") (pintype "passive"))
      (node (ref "U5") (pin "31") (pinfunction "IO19_31") (pintype "passive"))
    )
    (net (code "21") (name "/IO21") (class "Default")
      (node (ref "R16") (pin "2") (pinfunction "2_2") (pintype "passive"))
      (node (ref "U5") (pin "33") (pinfunction "IO21_33") (pintype "passive"))
    )
    (net (code "22") (name "/IO22") (class "Default")
      (node (ref "R14") (pin "2") (pinfunction "2_2") (pintype "passive"))
      (node (ref "U5") (pin "36") (pinfunction "IO22_36") (pintype "passive"))
    )
    (net (code "23") (name "/IO23") (class "Default")
      (node (ref "U5") (pin "37") (pinfunction "IO23_37") (pintype "passive"))
    )
    (net (code "24") (name "/IO25") (class "Default")
      (node (ref "U5") (pin "10") (pinfunction "IO25_10") (pintype "passive"))
    )
    (net (code "25") (name "/IO26") (class "Default")
      (node (ref "U5") (pin "11") (pinfunction "IO26_11") (pintype "passive"))
    )
    (net (code "26") (name "/IO35") (class "Default")
      (node (ref "U5") (pin "7") (pinfunction "IO35_7") (pintype "passive"))
    )
    (net (code "27") (name "/IO36") (class "Default")
      (node (ref "U5") (pin "4") (pinfunction "SENSOR_VP_4") (pintype "passive"))
    )
    (net (code "28") (name "/IO39") (class "Default")
      (node (ref "U5") (pin "5") (pinfunction "SENSOR_VN_5") (pintype "passive"))
    )
    (net (code "29") (name "/RS485_A+") (class "Default")
      (node (ref "F2") (pin "2") (pinfunction "2_2") (pintype "passive"))
      (node (ref "P1") (pin "4") (pinfunction "4_4") (pintype "passive"))
      (node (ref "P2") (pin "4") (pinfunction "4_4") (pintype "passive"))
      (node (ref "P4") (pin "4") (pinfunction "4_4") (pintype "passive"))
      (node (ref "P5") (pin "4") (pinfunction "4_4") (pintype "passive"))
    )
    (net (code "30") (name "/RS485_B-") (class "Default")
      (node (ref "F1") (pin "2") (pinfunction "2_2") (pintype "passive"))
      (node (ref "P1") (pin "3") (pinfunction "3_3") (pintype "passive"))
      (node (ref "P2") (pin "3") (pinfunction "3_3") (pintype "passive"))
      (node (ref "P4") (pin "3") (pinfunction "3_3") (pintype "passive"))
      (node (ref "P5") (pin "3") (pinfunction "3_3") (pintype "passive"))
    )
    (net (code "31") (name "/RST") (class "Default")
      (node (ref "P6") (pin "3") (pinfunction "3_3") (pintype "passive"))
      (node (ref "R32") (pin "1") (pinfunction "1_1") (pintype "passive"))
    )
    (net (code "32") (name "/RTS_CH340") (class "Default")
      (node (ref "Q5") (pin "2") (pinfunction "E_2") (pintype "passive"))
      (node (ref "Q6") (pin "1") (pinfunction "B_1") (pintype "passive"))
      (node (ref "U6") (pin "14") (pinfunction "RTS#_14") (pintype "passive"))
    )
    (net (code "33") (name "/RX0") (class "Default")
      (node (ref "LED4") (pin "2") (pinfunction "2_2") (pintype "passive"))
      (node (ref "U5") (pin "34") (pinfunction "RXD0_34") (pintype "passive"))
      (node (ref "U6") (pin "2") (pinfunction "TXD_2") (pintype "passive"))
    )
    (net (code "34") (name "/RX2") (class "Default")
      (node (ref "U1") (pin "1") (pinfunction "A_1") (pintype "input"))
      (node (ref "U1") (pin "4") (pinfunction "Y_4") (pintype "output"))
      (node (ref "U5") (pin "27") (pinfunction "IO16_27") (pintype "passive"))
    )
    (net (code "35") (name "/RX_CH340") (class "Default")
      (node (ref "LED5") (pin "2") (pinfunction "2_2") (pintype "passive"))
      (node (ref "U5") (pin "35") (pinfunction "TXD0_35") (pintype "passive"))
      (node (ref "U6") (pin "3") (pinfunction "RXD_3") (pintype "passive"))
    )
    (net (code "36") (name "/S1") (class "Default")
      (node (ref "J1") (pin "1") (pinfunction "1_1") (pintype "passive"))
      (node (ref "R8") (pin "2") (pinfunction "2_2") (pintype "passive"))
    )
    (net (code "37") (name "/S2") (class "Default")
      (node (ref "J2") (pin "1") (pinfunction "1_1") (pintype "passive"))
      (node (ref "R9") (pin "2") (pinfunction "2_2") (pintype "passive"))
    )
    (net (code "38") (name "/S3") (class "Default")
      (node (ref "J3") (pin "1") (pinfunction "1_1") (pintype "passive"))
      (node (ref "R10") (pin "2") (pinfunction "2_2") (pintype "passive"))
    )
    (net (code "39") (name "/S4") (class "Default")
      (node (ref "J4") (pin "1") (pinfunction "1_1") (pintype "passive"))
      (node (ref "R11") (pin "2") (pinfunction "2_2") (pintype "passive"))
    )
    (net (code "40") (name "/SCL_ADS") (class "Default")
      (node (ref "R14") (pin "1") (pinfunction "1_1") (pintype "passive"))
      (node (ref "R7") (pin "1") (pinfunction "1_1") (pintype "passive"))
      (node (ref "U3") (pin "10") (pinfunction "SCL_10") (pintype "input"))
    )
    (net (code "41") (name "/SDA_ADS") (class "Default")
      (node (ref "R16") (pin "1") (pinfunction "1_1") (pintype "passive"))
      (node (ref "R6") (pin "1") (pinfunction "1_1") (pintype "passive"))
      (node (ref "U3") (pin "9") (pinfunction "SDA_9") (pintype "bidirectional"))
    )
    (net (code "42") (name "/TX2") (class "Default")
      (node (ref "R15") (pin "2") (pinfunction "2_2") (pintype "passive"))
      (node (ref "U1") (pin "13") (pinfunction "A_13") (pintype "input"))
      (node (ref "U5") (pin "28") (pinfunction "IO17_28") (pintype "passive"))
    )
    (net (code "43") (name "3V3") (class "Default")
      (node (ref "C2") (pin "1") (pinfunction "1_1") (pintype "passive"))
      (node (ref "Cx3") (pin "2") (pinfunction "2_2") (pintype "passive"))
      (node (ref "Cx4") (pin "2") (pinfunction "2_2") (pintype "passive"))
      (node (ref "Cx5") (pin "1") (pinfunction "1_1") (pintype "passive"))
      (node (ref "R12") (pin "1") (pinfunction "1_1") (pintype "passive"))
      (node (ref "R13") (pin "2") (pinfunction "2_2") (pintype "passive"))
      (node (ref "R15") (pin "1") (pinfunction "1_1") (pintype "passive"))
      (node (ref "R27") (pin "1") (pinfunction "1_1") (pintype "passive"))
      (node (ref "R3") (pin "2") (pinfunction "2_2") (pintype "passive"))
      (node (ref "R35") (pin "1") (pinfunction "1_1") (pintype "passive"))
      (node (ref "R39") (pin "2") (pinfunction "2_2") (pintype "passive"))
      (node (ref "R4") (pin "2") (pinfunction "2_2") (pintype "passive"))
      (node (ref "R44") (pin "2") (pinfunction "2_2") (pintype "passive"))
      (node (ref "R6") (pin "2") (pinfunction "2_2") (pintype "passive"))
      (node (ref "R7") (pin "2") (pinfunction "2_2") (pintype "passive"))
      (node (ref "U1") (pin "14") (pinfunction "VCC_14") (pintype "passive"))
      (node (ref "U2") (pin "2") (pinfunction "OUT_2") (pintype "passive"))
      (node (ref "U2") (pin "4") (pinfunction "OUT_4") (pintype "passive"))
      (node (ref "U4") (pin "8") (pinfunction "VCC_8") (pintype "power_in"))
      (node (ref "U5") (pin "2") (pinfunction "3V3_2") (pintype "passive"))
    )
    (net (code "44") (name "5V") (class "Default")
      (node (ref "C1") (pin "1") (pinfunction "1_1") (pintype "passive"))
      (node (ref "C9") (pin "1") (pinfunction "1_1") (pintype "passive"))
      (node (ref "Cx9") (pin "2") (pinfunction "2_2") (pintype "passive"))
      (node (ref "DIO1") (pin "1") (pinfunction "A_1") (pintype "passive"))
      (node (ref "DIO3") (pin "1") (pinfunction "A_1") (pintype "passive"))
      (node (ref "DIO4") (pin "2") (pinfunction "K_2") (pintype "passive"))
      (node (ref "J1") (pin "2") (pinfunction "2_2") (pintype "passive"))
      (node (ref "J2") (pin "2") (pinfunction "2_2") (pintype "passive"))
      (node (ref "J3") (pin "2") (pinfunction "2_2") (pintype "passive"))
      (node (ref "J4") (pin "2") (pinfunction "2_2") (pintype "passive"))
      (node (ref "K1") (pin "A1") (pinfunction "COIL1_A1") (pintype "passive"))
      (node (ref "L1") (pin "2") (pinfunction "2_2") (pintype "passive"))
      (node (ref "P3") (pin "4") (pinfunction "4_4") (pintype "passive"))
      (node (ref "R45") (pin "2") (pinfunction "2_2") (pintype "passive"))
      (node (ref "U3") (pin "8") (pinfunction "VDD_8") (pintype "power_in"))
      (node (ref "U6") (pin "16") (pinfunction "VCC_16") (pintype "passive"))
      (node (ref "U7") (pin "4") (pinfunction "FB_4") (pintype "input"))
    )
    (net (code "45") (name "12V sensor") (class "Default")
      (node (ref "K1") (pin "14") (pinfunction "NO_14") (pintype "passive"))
      (node (ref "P1") (pin "1") (pinfunction "1_1") (pintype "passive"))
      (node (ref "P2") (pin "1") (pinfunction "1_1") (pintype "passive"))
      (node (ref "P4") (pin "1") (pinfunction "1_1") (pintype "passive"))
      (node (ref "P5") (pin "1") (pinfunction "1_1") (pintype "passive"))
    )
    (net (code "46") (name "COM") (class "Default")
      (node (ref "D1") (pin "2") (pinfunction "2_2") (pintype "passive"))
      (node (ref "D3") (pin "1") (pinfunction "1_1") (pintype "passive"))
    )
    (net (code "47") (name "GND") (class "Default")
      (node (ref "C1") (pin "2") (pinfunction "2_2") (pintype "passive"))
      (node (ref "C2") (pin "2") (pinfunction "2_2") (pintype "passive"))
      (node (ref "C3") (pin "1") (pinfunction "1_1") (pintype "passive"))
      (node (ref "C7") (pin "2") (pinfunction "2_2") (pintype "passive"))
      (node (ref "C9") (pin "2") (pinfunction "2_2") (pintype "passive"))
      (node (ref "Cx1") (pin "1") (pinfunction "1_1") (pintype "passive"))
      (node (ref "Cx2") (pin "1") (pinfunction "1_1") (pintype "passive"))
      (node (ref "Cx3") (pin "1") (pinfunction "1_1") (pintype "passive"))
      (node (ref "Cx4") (pin "1") (pinfunction "1_1") (pintype "passive"))
      (node (ref "Cx5") (pin "2") (pinfunction "2_2") (pintype "passive"))
      (node (ref "Cx6") (pin "2") (pinfunction "2_2") (pintype "passive"))
      (node (ref "Cx7") (pin "2") (pinfunction "2_2") (pintype "passive"))
      (node (ref "Cx8") (pin "1") (pinfunction "1_1") (pintype "passive"))
      (node (ref "Cx9") (pin "1") (pinfunction "1_1") (pintype "passive"))
      (node (ref "D5") (pin "1") (pinfunction "A_1") (pintype "passive"))
      (node (ref "DIO2") (pin "1") (pinfunction "A_1") (pintype "passive"))
      (node (ref "IO1") (pin "2") (pinfunction "2_2") (pintype "passive"))
      (node (ref "IO2") (pin "2") (pinfunction "2_2") (pintype "passive"))
      (node (ref "J1") (pin "3") (pinfunction "3_3") (pintype "passive"))
      (node (ref "J2") (pin "3") (pinfunction "3_3") (pintype "passive"))
      (node (ref "J3") (pin "3") (pinfunction "3_3") (pintype "passive"))
      (node (ref "J4") (pin "3") (pinfunction "3_3") (pintype "passive"))
      (node (ref "J5") (pin "A1") (pinfunction "GND_A_A1") (pintype "power_in"))
      (node (ref "J5") (pin "A12") (pinfunction "GND_A_A12") (pintype "power_in"))
      (node (ref "J5") (pin "B1") (pinfunction "GND_B_B1") (pintype "power_in"))
      (node (ref "J5") (pin "B12") (pinfunction "GND_B_B12") (pintype "power_in"))
      (node (ref "J5") (pin "S1") (pinfunction "SHELL_GND_S1") (pintype "power_in"))
      (node (ref "J5") (pin "S2") (pinfunction "SHELL_GND_S2") (pintype "power_in"))
      (node (ref "J5") (pin "S3") (pinfunction "SHELL_GND_S3") (pintype "power_in"))
      (node (ref "J5") (pin "S4") (pinfunction "SHELL_GND_S4") (pintype "power_in"))
      (node (ref "J8") (pin "2") (pinfunction "2_2") (pintype "passive"))
      (node (ref "LED1") (pin "2") (pinfunction "2_2") (pintype "passive"))
      (node (ref "LED2") (pin "2") (pinfunction "2_2") (pintype "passive"))
      (node (ref "LED3") (pin "2") (pinfunction "2_2") (pintype "passive"))
      (node (ref "LED6") (pin "2") (pinfunction "2_2") (pintype "passive"))
      (node (ref "LED7") (pin "2") (pinfunction "2_2") (pintype "passive"))
      (node (ref "LED8") (pin "2") (pinfunction "2_2") (pintype "passive"))
      (node (ref "P1") (pin "2") (pinfunction "2_2") (pintype "passive"))
      (node (ref "P10") (pin "2") (pinfunction "2_2") (pintype "passive"))
      (node (ref "P2") (pin "2") (pinfunction "2_2") (pintype "passive"))
      (node (ref "P3") (pin "2") (pinfunction "2_2") (pintype "passive"))
      (node (ref "P4") (pin "2") (pinfunction "2_2") (pintype "passive"))
      (node (ref "P5") (pin "2") (pinfunction "2_2") (pintype "passive"))
      (node (ref "P6") (pin "4") (pinfunction "4_4") (pintype "passive"))
      (node (ref "P7") (pin "2") (pinfunction "2_2") (pintype "passive"))
      (node (ref "P8") (pin "2") (pinfunction "2_2") (pintype "passive"))
      (node (ref "P9") (pin "2") (pinfunction "2_2") (pintype "passive"))
      (node (ref "Q1") (pin "1") (pinfunction "E_1") (pintype "passive"))
      (node (ref "Q2") (pin "3") (pinfunction "S_3") (pintype "passive"))
      (node (ref "Q3") (pin "3") (pinfunction "S_3") (pintype "passive"))
      (node (ref "Q4") (pin "2") (pinfunction "E_2") (pintype "passive"))
      (node (ref "Q7") (pin "3") (pinfunction "S_3") (pintype "passive"))
      (node (ref "Q8") (pin "3") (pinfunction "S_3") (pintype "passive"))
      (node (ref "R2") (pin "1") (pinfunction "1_1") (pintype "passive"))
      (node (ref "R23") (pin "2") (pinfunction "2_2") (pintype "passive"))
      (node (ref "R24") (pin "1") (pinfunction "1_1") (pintype "passive"))
      (node (ref "R25") (pin "2") (pinfunction "2_2") (pintype "passive"))
      (node (ref "R33") (pin "2") (pinfunction "2_2") (pintype "passive"))
      (node (ref "R34") (pin "2") (pinfunction "2_2") (pintype "passive"))
      (node (ref "R42") (pin "2") (pinfunction "2_2") (pintype "passive"))
      (node (ref "R43") (pin "2") (pinfunction "2_2") (pintype "passive"))
      (node (ref "R5") (pin "2") (pinfunction "2_2") (pintype "passive"))
      (node (ref "U1") (pin "7") (pinfunction "GND_7") (pintype "passive"))
      (node (ref "U2") (pin "1") (pinfunction "GND_1") (pintype "passive"))
      (node (ref "U3") (pin "3") (pinfunction "GND_3") (pintype "power_in"))
      (node (ref "U4") (pin "5") (pinfunction "GND_5") (pintype "power_in"))
      (node (ref "U5") (pin "1") (pinfunction "GND_1") (pintype "passive"))
      (node (ref "U5") (pin "15") (pinfunction "GND_15") (pintype "passive"))
      (node (ref "U5") (pin "38") (pinfunction "GND_38") (pintype "passive"))
      (node (ref "U5") (pin "39") (pinfunction "GND_39") (pintype "passive"))
      (node (ref "U6") (pin "1") (pinfunction "GND_1") (pintype "passive"))
      (node (ref "U7") (pin "3") (pinfunction "GND_3") (pintype "power_in"))
      (node (ref "U7") (pin "5") (pinfunction "~{ON}/OFF_5") (pintype "input"))
    )
    (net (code "48") (name "Net-(1-A)") (class "Default")
      (node (ref "1") (pin "1") (pinfunction "A_1") (pintype "passive"))
      (node (ref "C4") (pin "2") (pinfunction "2_2") (pintype "passive"))
      (node (ref "J6") (pin "2") (pinfunction "2_2") (pintype "passive"))
      (node (ref "Q2") (pin "2") (pinfunction "D_2") (pintype "passive"))
    )
    (net (code "49") (name "Net-(2-A)") (class "Default")
      (node (ref "2") (pin "1") (pinfunction "A_1") (pintype "passive"))
      (node (ref "C5") (pin "2") (pinfunction "2_2") (pintype "passive"))
      (node (ref "J7") (pin "2") (pinfunction "2_2") (pintype "passive"))
      (node (ref "Q3") (pin "2") (pinfunction "D_2") (pintype "passive"))
    )
    (net (code "50") (name "Net-(3-A)") (class "Default")
      (node (ref "3") (pin "1") (pinfunction "A_1") (pintype "passive"))
      (node (ref "C6") (pin "2") (pinfunction "2_2") (pintype "passive"))
      (node (ref "J9") (pin "2") (pinfunction "2_2") (pintype "passive"))
      (node (ref "Q7") (pin "2") (pinfunction "D_2") (pintype "passive"))
    )
    (net (code "51") (name "Net-(4-A)") (class "Default")
      (node (ref "4") (pin "1") (pinfunction "A_1") (pintype "passive"))
      (node (ref "C8") (pin "2") (pinfunction "2_2") (pintype "passive"))
      (node (ref "J10") (pin "2") (pinfunction "2_2") (pintype "passive"))
      (node (ref "Q8") (pin "2") (pinfunction "D_2") (pintype "passive"))
    )
    (net (code "52") (name "Net-(D5-K)") (class "Default")
      (node (ref "D5") (pin "2") (pinfunction "K_2") (pintype "passive"))
      (node (ref "L1") (pin "1") (pinfunction "1_1") (pintype "passive"))
      (node (ref "U7") (pin "2") (pinfunction "OUT_2") (pintype "power_in"))
    )
    (net (code "53") (name "Net-(DIO1-K)") (class "Default")
      (node (ref "Cx1") (pin "2") (pinfunction "2_2") (pintype "passive"))
      (node (ref "Cx2") (pin "2") (pinfunction "2_2") (pintype "passive"))
      (node (ref "DIO1") (pin "2") (pinfunction "K_2") (pintype "passive"))
      (node (ref "DIO2") (pin "2") (pinfunction "K_2") (pintype "passive"))
      (node (ref "U2") (pin "3") (pinfunction "IN_3") (pintype "passive"))
    )
    (net (code "54") (name "Net-(DIO3-K)") (class "Default")
      (node (ref "DIO3") (pin "2") (pinfunction "K_2") (pintype "passive"))
      (node (ref "K1") (pin "A2") (pinfunction "COIL2_A2") (pintype "passive"))
      (node (ref "Q1") (pin "2") (pinfunction "C_2") (pintype "passive"))
    )
    (net (code "55") (name "Net-(DIO4-A)") (class "Default")
      (node (ref "DIO4") (pin "1") (pinfunction "A_1") (pintype "passive"))
      (node (ref "J5") (pin "A4") (pinfunction "VBUS_A_A4") (pintype "power_in"))
      (node (ref "J5") (pin "A9") (pinfunction "VBUS_A_A9") (pintype "power_in"))
      (node (ref "J5") (pin "B4") (pinfunction "VBUS_B_B4") (pintype "power_in"))
      (node (ref "J5") (pin "B9") (pinfunction "VBUS_B_B9") (pintype "power_in"))
    )
    (net (code "56") (name "Net-(IO2-Pad1)") (class "Default")
      (node (ref "IO2") (pin "1") (pinfunction "1_1") (pintype "passive"))
      (node (ref "R36") (pin "1") (pinfunction "1_1") (pintype "passive"))
    )
    (net (code "57") (name "Net-(J5-CC1)") (class "Default")
      (node (ref "J5") (pin "A5") (pinfunction "CC1_A5") (pintype "bidirectional"))
      (node (ref "R24") (pin "2") (pinfunction "2_2") (pintype "passive"))
    )
    (net (code "58") (name "Net-(J5-CC2)") (class "Default")
      (node (ref "J5") (pin "B5") (pinfunction "CC2_B5") (pintype "bidirectional"))
      (node (ref "R25") (pin "1") (pinfunction "1_1") (pintype "passive"))
    )
    (net (code "59") (name "Net-(LED1-Pad1)") (class "Default")
      (node (ref "LED1") (pin "1") (pinfunction "1_1") (pintype "passive"))
      (node (ref "R1") (pin "2") (pinfunction "2_2") (pintype "passive"))
    )
    (net (code "60") (name "Net-(LED2-Pad1)") (class "Default")
      (node (ref "LED2") (pin "1") (pinfunction "1_1") (pintype "passive"))
      (node (ref "R3") (pin "1") (pinfunction "1_1") (pintype "passive"))
    )
    (net (code "61") (name "Net-(LED3-Pad1)") (class "Default")
      (node (ref "LED3") (pin "1") (pinfunction "1_1") (pintype "passive"))
      (node (ref "R17") (pin "2") (pinfunction "2_2") (pintype "passive"))
    )
    (net (code "62") (name "Net-(LED4-Pad1)") (class "Default")
      (node (ref "LED4") (pin "1") (pinfunction "1_1") (pintype "passive"))
      (node (ref "R39") (pin "1") (pinfunction "1_1") (pintype "passive"))
    )
    (net (code "63") (name "Net-(LED5-Pad1)") (class "Default")
      (node (ref "LED5") (pin "1") (pinfunction "1_1") (pintype "passive"))
      (node (ref "R44") (pin "1") (pinfunction "1_1") (pintype "passive"))
    )
    (net (code "64") (name "Net-(LED6-Pad1)") (class "Default")
      (node (ref "LED6") (pin "1") (pinfunction "1_1") (pintype "passive"))
      (node (ref "R46") (pin "1") (pinfunction "1_1") (pintype "passive"))
    )
    (net (code "65") (name "Net-(LED7-Pad1)") (class "Default")
      (node (ref "LED7") (pin "1") (pinfunction "1_1") (pintype "passive"))
      (node (ref "R45") (pin "1") (pinfunction "1_1") (pintype "passive"))
    )
    (net (code "66") (name "Net-(LED8-Pad1)") (class "Default")
      (node (ref "LED8") (pin "1") (pinfunction "1_1") (pintype "passive"))
      (node (ref "R47") (pin "1") (pinfunction "1_1") (pintype "passive"))
    )
    (net (code "67") (name "Net-(P3-Pad1)") (class "Default")
      (node (ref "P3") (pin "1") (pinfunction "1_1") (pintype "passive"))
      (node (ref "R19") (pin "1") (pinfunction "1_1") (pintype "passive"))
    )
    (net (code "68") (name "Net-(P3-Pad3)") (class "Default")
      (node (ref "P3") (pin "3") (pinfunction "3_3") (pintype "passive"))
      (node (ref "R20") (pin "2") (pinfunction "2_2") (pintype "passive"))
    )
    (net (code "69") (name "Net-(P6-Pad1)") (class "Default")
      (node (ref "P6") (pin "1") (pinfunction "1_1") (pintype "passive"))
      (node (ref "R21") (pin "1") (pinfunction "1_1") (pintype "passive"))
    )
    (net (code "70") (name "Net-(P6-Pad2)") (class "Default")
      (node (ref "P6") (pin "2") (pinfunction "2_2") (pintype "passive"))
      (node (ref "R22") (pin "1") (pinfunction "1_1") (pintype "passive"))
    )
    (net (code "71") (name "Net-(P7-Pad1)") (class "Default")
      (node (ref "P7") (pin "1") (pinfunction "1_1") (pintype "passive"))
      (node (ref "R26") (pin "2") (pinfunction "2_2") (pintype "passive"))
    )
    (net (code "72") (name "Net-(P7-Pad3)") (class "Default")
      (node (ref "P7") (pin "3") (pinfunction "3_3") (pintype "passive"))
      (node (ref "R30") (pin "2") (pinfunction "2_2") (pintype "passive"))
    )
    (net (code "73") (name "Net-(P8-Pad1)") (class "Default")
      (node (ref "P8") (pin "1") (pinfunction "1_1") (pintype "passive"))
      (node (ref "R29") (pin "2") (pinfunction "2_2") (pintype "passive"))
    )
    (net (code "74") (name "Net-(P8-Pad3)") (class "Default")
      (node (ref "P8") (pin "3") (pinfunction "3_3") (pintype "passive"))
      (node (ref "R31") (pin "2") (pinfunction "2_2") (pintype "passive"))
    )
    (net (code "75") (name "Net-(P9-Pad1)") (class "Default")
      (node (ref "P9") (pin "1") (pinfunction "1_1") (pintype "passive"))
      (node (ref "R37") (pin "2") (pinfunction "2_2") (pintype "passive"))
    )
    (net (code "76") (name "Net-(P9-Pad3)") (class "Default")
      (node (ref "P9") (pin "3") (pinfunction "3_3") (pintype "passive"))
      (node (ref "R40") (pin "2") (pinfunction "2_2") (pintype "passive"))
    )
    (net (code "77") (name "Net-(P10-Pad1)") (class "Default")
      (node (ref "P10") (pin "1") (pinfunction "1_1") (pintype "passive"))
      (node (ref "R38") (pin "2") (pinfunction "2_2") (pintype "passive"))
    )
    (net (code "78") (name "Net-(P10-Pad3)") (class "Default")
      (node (ref "P10") (pin "3") (pinfunction "3_3") (pintype "passive"))
      (node (ref "R41") (pin "2") (pinfunction "2_2") (pintype "passive"))
    )
    (net (code "79") (name "Net-(Q1-B)") (class "Default")
      (node (ref "Q1") (pin "3") (pinfunction "B_3") (pintype "passive"))
      (node (ref "R20") (pin "1") (pinfunction "1_1") (pintype "passive"))
      (node (ref "R23") (pin "1") (pinfunction "1_1") (pintype "passive"))
    )
    (net (code "80") (name "Net-(Q2-G)") (class "Default")
      (node (ref "Q2") (pin "1") (pinfunction "G_1") (pintype "passive"))
      (node (ref "R30") (pin "1") (pinfunction "1_1") (pintype "passive"))
      (node (ref "R33") (pin "1") (pinfunction "1_1") (pintype "passive"))
    )
    (net (code "81") (name "Net-(Q3-G)") (class "Default")
      (node (ref "Q3") (pin "1") (pinfunction "G_1") (pintype "passive"))
      (node (ref "R31") (pin "1") (pinfunction "1_1") (pintype "passive"))
      (node (ref "R34") (pin "1") (pinfunction "1_1") (pintype "passive"))
    )
    (net (code "82") (name "Net-(Q4-B)") (class "Default")
      (node (ref "Q4") (pin "1") (pinfunction "B_1") (pintype "passive"))
      (node (ref "R32") (pin "2") (pinfunction "2_2") (pintype "passive"))
    )
    (net (code "83") (name "Net-(Q4-C)") (class "Default")
      (node (ref "IO1") (pin "1") (pinfunction "1_1") (pintype "passive"))
      (node (ref "Q4") (pin "3") (pinfunction "C_3") (pintype "passive"))
      (node (ref "R28") (pin "2") (pinfunction "2_2") (pintype "passive"))
    )
    (net (code "84") (name "Net-(Q7-G)") (class "Default")
      (node (ref "Q7") (pin "1") (pinfunction "G_1") (pintype "passive"))
      (node (ref "R40") (pin "1") (pinfunction "1_1") (pintype "passive"))
      (node (ref "R42") (pin "1") (pinfunction "1_1") (pintype "passive"))
    )
    (net (code "85") (name "Net-(Q8-G)") (class "Default")
      (node (ref "Q8") (pin "1") (pinfunction "G_1") (pintype "passive"))
      (node (ref "R41") (pin "1") (pinfunction "1_1") (pintype "passive"))
      (node (ref "R43") (pin "1") (pinfunction "1_1") (pintype "passive"))
    )
    (net (code "86") (name "Net-(U1A-Y)") (class "Default")
      (node (ref "R1") (pin "1") (pinfunction "1_1") (pintype "passive"))
      (node (ref "U1") (pin "2") (pinfunction "Y_2") (pintype "output"))
    )
    (net (code "87") (name "Net-(U1B-A)") (class "Default")
      (node (ref "U1") (pin "3") (pinfunction "A_3") (pintype "input"))
      (node (ref "U1") (pin "6") (pinfunction "Y_6") (pintype "output"))
    )
    (net (code "88") (name "Net-(U1C-A)") (class "Default")
      (node (ref "R12") (pin "2") (pinfunction "2_2") (pintype "passive"))
      (node (ref "U1") (pin "5") (pinfunction "A_5") (pintype "input"))
      (node (ref "U4") (pin "1") (pinfunction "RO_1") (pintype "output"))
    )
    (net (code "89") (name "Net-(U1D-A)") (class "Default")
      (node (ref "R17") (pin "1") (pinfunction "1_1") (pintype "passive"))
      (node (ref "U1") (pin "12") (pinfunction "Y_12") (pintype "output"))
      (node (ref "U1") (pin "9") (pinfunction "A_9") (pintype "input"))
    )
    (net (code "90") (name "Net-(U1D-Y)") (class "Default")
      (node (ref "D4") (pin "2") (pinfunction "2_2") (pintype "passive"))
      (node (ref "R18") (pin "1") (pinfunction "1_1") (pintype "passive"))
      (node (ref "U1") (pin "8") (pinfunction "Y_8") (pintype "output"))
      (node (ref "U4") (pin "4") (pinfunction "DI_4") (pintype "input"))
    )
    (net (code "91") (name "Net-(U1E-A)") (class "Default")
      (node (ref "Cx6") (pin "1") (pinfunction "1_1") (pintype "passive"))
      (node (ref "D4") (pin "1") (pinfunction "1_1") (pintype "passive"))
      (node (ref "R18") (pin "2") (pinfunction "2_2") (pintype "passive"))
      (node (ref "U1") (pin "11") (pinfunction "A_11") (pintype "input"))
    )
    (net (code "92") (name "Net-(U1E-Y)") (class "Default")
      (node (ref "U1") (pin "10") (pinfunction "Y_10") (pintype "output"))
      (node (ref "U4") (pin "2") (pinfunction "~{RE}_2") (pintype "input"))
      (node (ref "U4") (pin "3") (pinfunction "DE_3") (pintype "input"))
    )
    (net (code "93") (name "Net-(U3-ADDR)") (class "Default")
      (node (ref "R5") (pin "1") (pinfunction "1_1") (pintype "passive"))
      (node (ref "U3") (pin "1") (pinfunction "ADDR_1") (pintype "input"))
    )
    (net (code "94") (name "Net-(U3-AIN0)") (class "Default")
      (node (ref "R8") (pin "1") (pinfunction "1_1") (pintype "passive"))
      (node (ref "U3") (pin "4") (pinfunction "AIN0_4") (pintype "input"))
    )
    (net (code "95") (name "Net-(U3-AIN1)") (class "Default")
      (node (ref "R9") (pin "1") (pinfunction "1_1") (pintype "passive"))
      (node (ref "U3") (pin "5") (pinfunction "AIN1_5") (pintype "input"))
    )
    (net (code "96") (name "Net-(U3-AIN2)") (class "Default")
      (node (ref "R10") (pin "1") (pinfunction "1_1") (pintype "passive"))
      (node (ref "U3") (pin "6") (pinfunction "AIN2_6") (pintype "input"))
    )
    (net (code "97") (name "Net-(U3-AIN3)") (class "Default")
      (node (ref "R11") (pin "1") (pinfunction "1_1") (pintype "passive"))
      (node (ref "U3") (pin "7") (pinfunction "AIN3_7") (pintype "input"))
    )
    (net (code "98") (name "Net-(U3-ALERT{slash}RDY)") (class "Default")
      (node (ref "R4") (pin "1") (pinfunction "1_1") (pintype "passive"))
      (node (ref "U3") (pin "2") (pinfunction "ALERT/RDY_2") (pintype "output"))
    )
    (net (code "99") (name "Net-(U4-A)") (class "Default")
      (node (ref "D2") (pin "1") (pinfunction "1_1") (pintype "passive"))
      (node (ref "D3") (pin "2") (pinfunction "2_2") (pintype "passive"))
      (node (ref "F2") (pin "1") (pinfunction "1_1") (pintype "passive"))
      (node (ref "R13") (pin "1") (pinfunction "1_1") (pintype "passive"))
      (node (ref "U4") (pin "6") (pinfunction "A_6") (pintype "bidirectional"))
    )
    (net (code "100") (name "Net-(U4-B)") (class "Default")
      (node (ref "D1") (pin "1") (pinfunction "1_1") (pintype "passive"))
      (node (ref "D2") (pin "2") (pinfunction "2_2") (pintype "passive"))
      (node (ref "F1") (pin "1") (pinfunction "1_1") (pintype "passive"))
      (node (ref "R2") (pin "2") (pinfunction "2_2") (pintype "passive"))
      (node (ref "U4") (pin "7") (pinfunction "B_7") (pintype "bidirectional"))
    )
    (net (code "101") (name "Net-(U6-V3)") (class "Default")
      (node (ref "C3") (pin "2") (pinfunction "2_2") (pintype "passive"))
      (node (ref "U6") (pin "4") (pinfunction "V3_4") (pintype "passive"))
    )
    (net (code "102") (name "VIN") (class "Default")
      (node (ref "1") (pin "2") (pinfunction "K_2") (pintype "passive"))
      (node (ref "2") (pin "2") (pinfunction "K_2") (pintype "passive"))
      (node (ref "3") (pin "2") (pinfunction "K_2") (pintype "passive"))
      (node (ref "4") (pin "2") (pinfunction "K_2") (pintype "passive"))
      (node (ref "C4") (pin "1") (pinfunction "1_1") (pintype "passive"))
      (node (ref "C5") (pin "1") (pinfunction "1_1") (pintype "passive"))
      (node (ref "C6") (pin "1") (pinfunction "1_1") (pintype "passive"))
      (node (ref "C7") (pin "1") (pinfunction "1_1") (pintype "passive"))
      (node (ref "C8") (pin "1") (pinfunction "1_1") (pintype "passive"))
      (node (ref "Cx8") (pin "2") (pinfunction "2_2") (pintype "passive"))
      (node (ref "J10") (pin "1") (pinfunction "1_1") (pintype "passive"))
      (node (ref "J6") (pin "1") (pinfunction "1_1") (pintype "passive"))
      (node (ref "J7") (pin "1") (pinfunction "1_1") (pintype "passive"))
      (node (ref "J8") (pin "1") (pinfunction "1_1") (pintype "passive"))
      (node (ref "J9") (pin "1") (pinfunction "1_1") (pintype "passive"))
      (node (ref "K1") (pin "11") (pinfunction "COM_11") (pintype "passive"))
      (node (ref "P10") (pin "4") (pinfunction "4_4") (pintype "passive"))
      (node (ref "P7") (pin "4") (pinfunction "4_4") (pintype "passive"))
      (node (ref "P8") (pin "4") (pinfunction "4_4") (pintype "passive"))
      (node (ref "P9") (pin "4") (pinfunction "4_4") (pintype "passive"))
      (node (ref "U7") (pin "1") (pinfunction "VIN_1") (pintype "power_in"))
    )
    (net (code "103") (name "unconnected-(J5-SBU1-PadA8)") (class "Default")
      (node (ref "J5") (pin "A8") (pinfunction "SBU1_A8") (pintype "bidirectional+no_connect"))
    )
    (net (code "104") (name "unconnected-(J5-SBU2-PadB8)") (class "Default")
      (node (ref "J5") (pin "B8") (pinfunction "SBU2_B8") (pintype "bidirectional+no_connect"))
    )
    (net (code "105") (name "unconnected-(K1-NC-Pad12)") (class "Default")
      (node (ref "K1") (pin "12") (pinfunction "NC_12") (pintype "passive"))
    )
    (net (code "106") (name "unconnected-(U5-CLK-Pad20)") (class "Default")
      (node (ref "U5") (pin "20") (pinfunction "CLK_20") (pintype "passive"))
    )
    (net (code "107") (name "unconnected-(U5-CMD-Pad19)") (class "Default")
      (node (ref "U5") (pin "19") (pinfunction "CMD_19") (pintype "passive"))
    )
    (net (code "108") (name "unconnected-(U5-NC-Pad32)") (class "Default")
      (node (ref "U5") (pin "32") (pinfunction "NC_32") (pintype "passive"))
    )
    (net (code "109") (name "unconnected-(U5-SD0-Pad21)") (class "Default")
      (node (ref "U5") (pin "21") (pinfunction "SD0_21") (pintype "passive"))
    )
    (net (code "110") (name "unconnected-(U5-SD1-Pad22)") (class "Default")
      (node (ref "U5") (pin "22") (pinfunction "SD1_22") (pintype "passive"))
    )
    (net (code "111") (name "unconnected-(U6-CTS#-Pad9)") (class "Default")
      (node (ref "U6") (pin "9") (pinfunction "CTS#_9") (pintype "passive+no_connect"))
    )
    (net (code "112") (name "unconnected-(U6-DCD#-Pad12)") (class "Default")
      (node (ref "U6") (pin "12") (pinfunction "DCD#_12") (pintype "passive+no_connect"))
    )
    (net (code "113") (name "unconnected-(U6-DSR#-Pad10)") (class "Default")
      (node (ref "U6") (pin "10") (pinfunction "DSR#_10") (pintype "passive+no_connect"))
    )
    (net (code "114") (name "unconnected-(U6-NC-Pad7)") (class "Default")
      (node (ref "U6") (pin "7") (pinfunction "NC_7") (pintype "passive+no_connect"))
    )
    (net (code "115") (name "unconnected-(U6-NC-Pad8)") (class "Default")
      (node (ref "U6") (pin "8") (pinfunction "NC_8") (pintype "passive+no_connect"))
    )
    (net (code "116") (name "unconnected-(U6-R232-Pad15)") (class "Default")
      (node (ref "U6") (pin "15") (pinfunction "R232_15") (pintype "passive+no_connect"))
    )
    (net (code "117") (name "unconnected-(U6-RI#-Pad11)") (class "Default")
      (node (ref "U6") (pin "11") (pinfunction "RI#_11") (pintype "passive+no_connect"))
    )
  )
)
